# driver_isolated_opto.net
KiCad netlist of a schematic drawn in Altium Designer
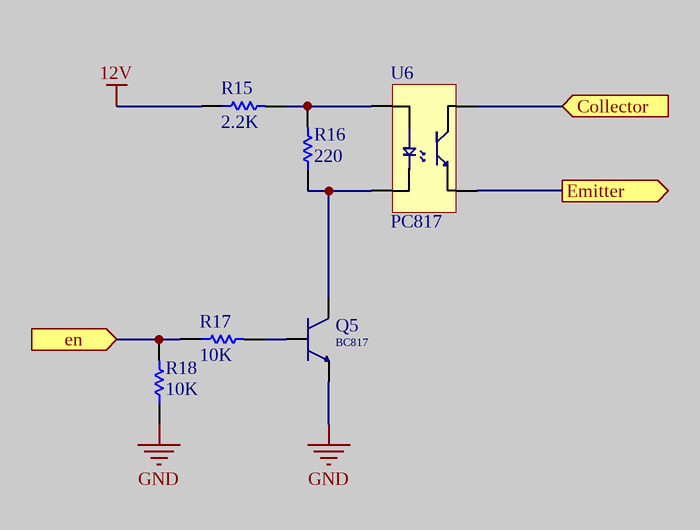
[diagram p0: driver_isolated_opto.SchDoc]

(export (version "E")
  (design (tool "Eeschema 10.0.6"))
  (components
    (comp (ref "Q5")
      (value "NPN transistor")
      (footprint "NPN")
      (description "45 V, 0.5 A")
      (fields (field (name "TRANSISTOR") "BC817"))
      (libsource (lib "eLIB") (part "BC817"))
    )
    (comp (ref "R15")
      (value "2.2K")
      (footprint "RESC0603")
      (description "0603,0.1W")
      (fields (field (name "PUBLISHER") "Altium Limited"))
      (libsource (lib "eLIB") (part "Resistor"))
    )
    (comp (ref "R16")
      (value "220")
      (footprint "RESC0603")
      (description "0603,0.1W")
      (fields (field (name "PUBLISHER") "Altium Limited"))
      (libsource (lib "eLIB") (part "Resistor"))
    )
    (comp (ref "R17")
      (value "10K")
      (footprint "RESC0603")
      (description "0603,0.1W")
      (fields (field (name "PUBLISHER") "Altium Limited"))
      (libsource (lib "eLIB") (part "Resistor"))
    )
    (comp (ref "R18")
      (value "10K")
      (footprint "RESC0603")
      (description "0603,0.1W")
      (fields (field (name "PUBLISHER") "Altium Limited"))
      (libsource (lib "eLIB") (part "Resistor"))
    )
    (comp (ref "U6")
      (value "PC817")
      (footprint "PC817")
      (description "PC817 optocoupler")
      (libsource (lib "eLIB") (part "PC817"))
    )
  )
  (nets
    (net (code "1") (name "/Collector") (class "Default")
      (node (ref "U6") (pin "4") (pinfunction "4_4") (pintype "passive"))
    )
    (net (code "2") (name "/Emitter") (class "Default")
      (node (ref "U6") (pin "3") (pinfunction "3_3") (pintype "passive"))
    )
    (net (code "3") (name "/en") (class "Default")
      (node (ref "R17") (pin "1") (pinfunction "1_1") (pintype "passive"))
      (node (ref "R18") (pin "2") (pinfunction "2_2") (pintype "passive"))
    )
    (net (code "4") (name "12V") (class "Default")
      (node (ref "R15") (pin "1") (pinfunction "1_1") (pintype "passive"))
    )
    (net (code "5") (name "GND") (class "Default")
      (node (ref "Q5") (pin "2") (pinfunction "E_2") (pintype "passive"))
      (node (ref "R18") (pin "1") (pinfunction "1_1") (pintype "passive"))
    )
    (net (code "6") (name "Net-(Q5-B)") (class "Default")
      (node (ref "Q5") (pin "1") (pinfunction "B_1") (pintype "passive"))
      (node (ref "R17") (pin "2") (pinfunction "2_2") (pintype "passive"))
    )
    (net (code "7") (name "Net-(Q5-C)") (class "Default")
      (node (ref "Q5") (pin "3") (pinfunction "C_3") (pintype "passive"))
      (node (ref "R16") (pin "1") (pinfunction "1_1") (pintype "passive"))
      (node (ref "U6") (pin "2") (pinfunction "2_2") (pintype "passive"))
    )
    (net (code "8") (name "Net-(R15-Pad2)") (class "Default")
      (node (ref "R15") (pin "2") (pinfunction "2_2") (pintype "passive"))
      (node (ref "R16") (pin "2") (pinfunction "2_2") (pintype "passive"))
      (node (ref "U6") (pin "1") (pinfunction "1_1") (pintype "passive"))
    )
  )
)
